# owc-receiver-v5.net
KiCad netlist of a schematic drawn in EAGLE
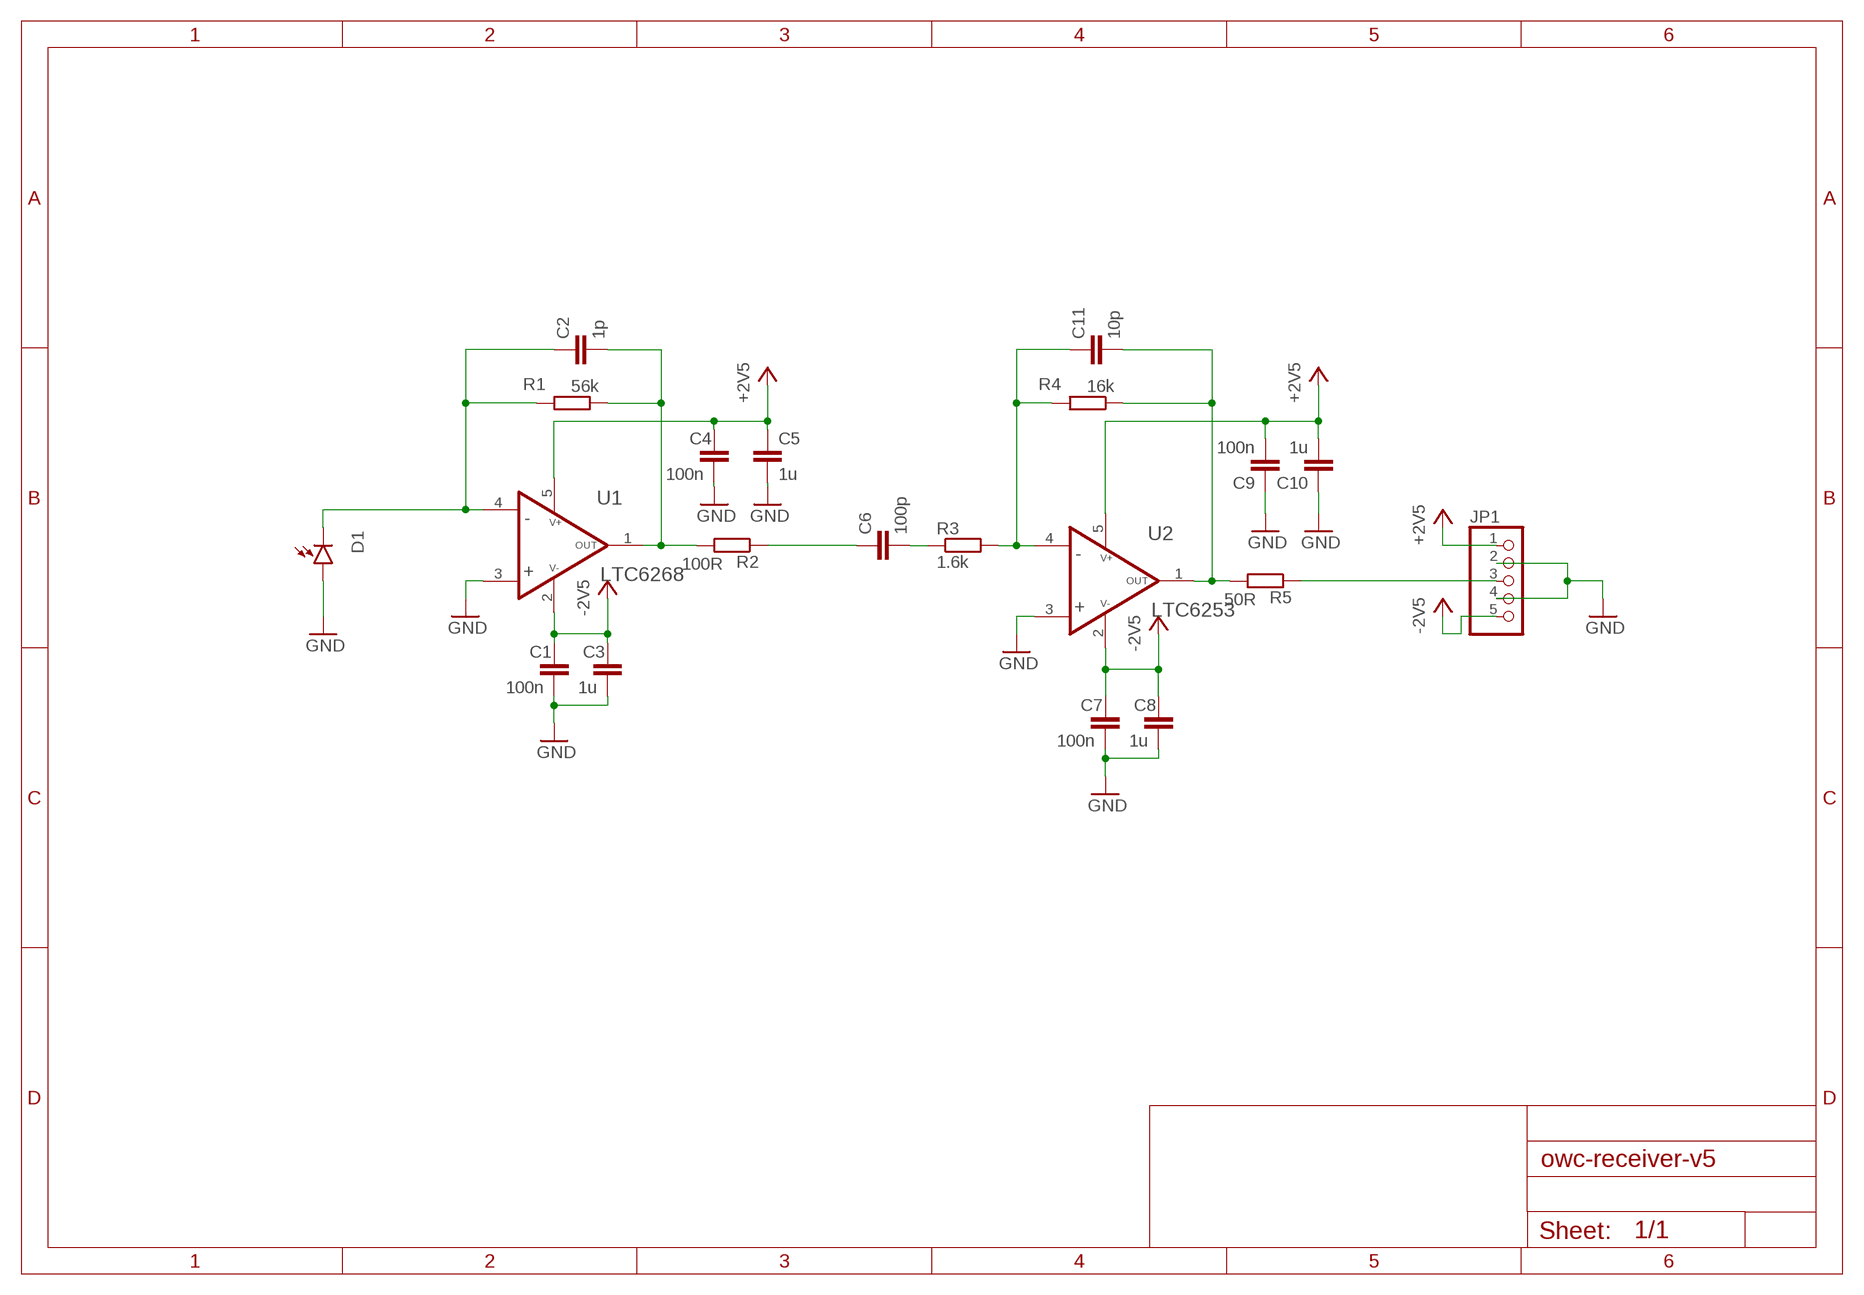
[diagram p0: schematic, sheet 1]

(export (version "E")
  (design (tool "Eeschema 10.0.6"))
  (components
    (comp (ref "C1")
      (value "100n")
      (footprint "eagle-import:C0805")
      (libsource (lib "eagle-import") (part "C-EUC0805"))
    )
    (comp (ref "C2")
      (value "1p")
      (footprint "eagle-import:C0805")
      (libsource (lib "eagle-import") (part "C-EUC0805"))
    )
    (comp (ref "C3")
      (value "1u")
      (footprint "eagle-import:C0805")
      (libsource (lib "eagle-import") (part "C-EUC0805"))
    )
    (comp (ref "C4")
      (value "100n")
      (footprint "eagle-import:C0805")
      (libsource (lib "eagle-import") (part "C-EUC0805"))
    )
    (comp (ref "C5")
      (value "1u")
      (footprint "eagle-import:C0805")
      (libsource (lib "eagle-import") (part "C-EUC0805"))
    )
    (comp (ref "C6")
      (value "100p")
      (footprint "eagle-import:C0805")
      (libsource (lib "eagle-import") (part "C-EUC0805"))
    )
    (comp (ref "C7")
      (value "100n")
      (footprint "eagle-import:C0805")
      (libsource (lib "eagle-import") (part "C-EUC0805"))
    )
    (comp (ref "C8")
      (value "1u")
      (footprint "eagle-import:C0805")
      (libsource (lib "eagle-import") (part "C-EUC0805"))
    )
    (comp (ref "C9")
      (value "100n")
      (footprint "eagle-import:C0805")
      (libsource (lib "eagle-import") (part "C-EUC0805"))
    )
    (comp (ref "C10")
      (value "1u")
      (footprint "eagle-import:C0805")
      (libsource (lib "eagle-import") (part "C-EUC0805"))
    )
    (comp (ref "C11")
      (value "10p")
      (footprint "eagle-import:C0805")
      (libsource (lib "eagle-import") (part "C-EUC0805"))
    )
    (comp (ref "D1")
      (value "PHOTODIODE5MM")
      (footprint "eagle-import:LED5MM")
      (libsource (lib "eagle-import") (part "PHOTODIODE5MM"))
    )
    (comp (ref "JP1")
      (value "PINHD-1X5")
      (footprint "eagle-import:1X05")
      (libsource (lib "eagle-import") (part "PINHD-1X5"))
    )
    (comp (ref "R1")
      (value "56k")
      (footprint "eagle-import:R0805")
      (libsource (lib "eagle-import") (part "R-EU_R0805"))
    )
    (comp (ref "R2")
      (value "100R")
      (footprint "eagle-import:R0805")
      (libsource (lib "eagle-import") (part "R-EU_R0805"))
    )
    (comp (ref "R3")
      (value "1.6k")
      (footprint "eagle-import:R0805")
      (libsource (lib "eagle-import") (part "R-EU_R0805"))
    )
    (comp (ref "R4")
      (value "16k")
      (footprint "eagle-import:R0805")
      (libsource (lib "eagle-import") (part "R-EU_R0805"))
    )
    (comp (ref "R5")
      (value "50R")
      (footprint "eagle-import:R0805")
      (libsource (lib "eagle-import") (part "R-EU_R0805"))
    )
    (comp (ref "U1")
      (value "LTC6268")
      (footprint "eagle-import:SOT23-5L")
      (libsource (lib "eagle-import") (part "LMH6629MF"))
    )
    (comp (ref "U2")
      (value "LTC6253")
      (footprint "eagle-import:SOT23-5L")
      (libsource (lib "eagle-import") (part "LMH6629MF"))
    )
  )
  (nets
    (net (code "1") (name "+2V5") (class "Default")
      (node (ref "C10") (pin "2") (pinfunction "2_2") (pintype "passive"))
      (node (ref "C4") (pin "1") (pinfunction "1_1") (pintype "passive"))
      (node (ref "C5") (pin "1") (pinfunction "1_1") (pintype "passive"))
      (node (ref "C9") (pin "2") (pinfunction "2_2") (pintype "passive"))
      (node (ref "JP1") (pin "1") (pinfunction "1_1") (pintype "passive"))
      (node (ref "U1") (pin "5") (pinfunction "V+_5") (pintype "power_in"))
      (node (ref "U2") (pin "5") (pinfunction "V+_5") (pintype "power_in"))
    )
    (net (code "2") (name "-2V5") (class "Default")
      (node (ref "C1") (pin "1") (pinfunction "1_1") (pintype "passive"))
      (node (ref "C3") (pin "1") (pinfunction "1_1") (pintype "passive"))
      (node (ref "C7") (pin "1") (pinfunction "1_1") (pintype "passive"))
      (node (ref "C8") (pin "1") (pinfunction "1_1") (pintype "passive"))
      (node (ref "JP1") (pin "5") (pinfunction "5_5") (pintype "passive"))
      (node (ref "U1") (pin "2") (pinfunction "V-_2") (pintype "power_in"))
      (node (ref "U2") (pin "2") (pinfunction "V-_2") (pintype "power_in"))
    )
    (net (code "3") (name "GND") (class "Default")
      (node (ref "C1") (pin "2") (pinfunction "2_2") (pintype "passive"))
      (node (ref "C10") (pin "1") (pinfunction "1_1") (pintype "passive"))
      (node (ref "C3") (pin "2") (pinfunction "2_2") (pintype "passive"))
      (node (ref "C4") (pin "2") (pinfunction "2_2") (pintype "passive"))
      (node (ref "C5") (pin "2") (pinfunction "2_2") (pintype "passive"))
      (node (ref "C7") (pin "2") (pinfunction "2_2") (pintype "passive"))
      (node (ref "C8") (pin "2") (pinfunction "2_2") (pintype "passive"))
      (node (ref "C9") (pin "1") (pinfunction "1_1") (pintype "passive"))
      (node (ref "D1") (pin "A") (pinfunction "A_A") (pintype "passive"))
      (node (ref "JP1") (pin "2") (pinfunction "2_2") (pintype "passive"))
      (node (ref "JP1") (pin "4") (pinfunction "4_4") (pintype "passive"))
      (node (ref "U1") (pin "3") (pinfunction "IN+_3") (pintype "input"))
      (node (ref "U2") (pin "3") (pinfunction "IN+_3") (pintype "input"))
    )
    (net (code "4") (name "Net-(C6-Pad1)") (class "Default")
      (node (ref "C6") (pin "1") (pinfunction "1_1") (pintype "passive"))
      (node (ref "R2") (pin "1") (pinfunction "1_1") (pintype "passive"))
    )
    (net (code "5") (name "Net-(C6-Pad2)") (class "Default")
      (node (ref "C6") (pin "2") (pinfunction "2_2") (pintype "passive"))
      (node (ref "R3") (pin "1") (pinfunction "1_1") (pintype "passive"))
    )
    (net (code "6") (name "Net-(D1-C)") (class "Default")
      (node (ref "C2") (pin "1") (pinfunction "1_1") (pintype "passive"))
      (node (ref "D1") (pin "K") (pinfunction "C_K") (pintype "passive"))
      (node (ref "R1") (pin "2") (pinfunction "2_2") (pintype "passive"))
      (node (ref "U1") (pin "4") (pinfunction "IN-_4") (pintype "input"))
    )
    (net (code "7") (name "Net-(JP1-Pad3)") (class "Default")
      (node (ref "JP1") (pin "3") (pinfunction "3_3") (pintype "passive"))
      (node (ref "R5") (pin "1") (pinfunction "1_1") (pintype "passive"))
    )
    (net (code "8") (name "Net-(U1-OUT)") (class "Default")
      (node (ref "C2") (pin "2") (pinfunction "2_2") (pintype "passive"))
      (node (ref "R1") (pin "1") (pinfunction "1_1") (pintype "passive"))
      (node (ref "R2") (pin "2") (pinfunction "2_2") (pintype "passive"))
      (node (ref "U1") (pin "1") (pinfunction "OUT_1") (pintype "output"))
    )
    (net (code "9") (name "Net-(U2-IN-)") (class "Default")
      (node (ref "C11") (pin "1") (pinfunction "1_1") (pintype "passive"))
      (node (ref "R3") (pin "2") (pinfunction "2_2") (pintype "passive"))
      (node (ref "R4") (pin "2") (pinfunction "2_2") (pintype "passive"))
      (node (ref "U2") (pin "4") (pinfunction "IN-_4") (pintype "input"))
    )
    (net (code "10") (name "Net-(U2-OUT)") (class "Default")
      (node (ref "C11") (pin "2") (pinfunction "2_2") (pintype "passive"))
      (node (ref "R4") (pin "1") (pinfunction "1_1") (pintype "passive"))
      (node (ref "R5") (pin "2") (pinfunction "2_2") (pintype "passive"))
      (node (ref "U2") (pin "1") (pinfunction "OUT_1") (pintype "output"))
    )
  )
)
